# USB_IF_STM_Lpt_v3.net
KiCad netlist of a schematic drawn in EAGLE
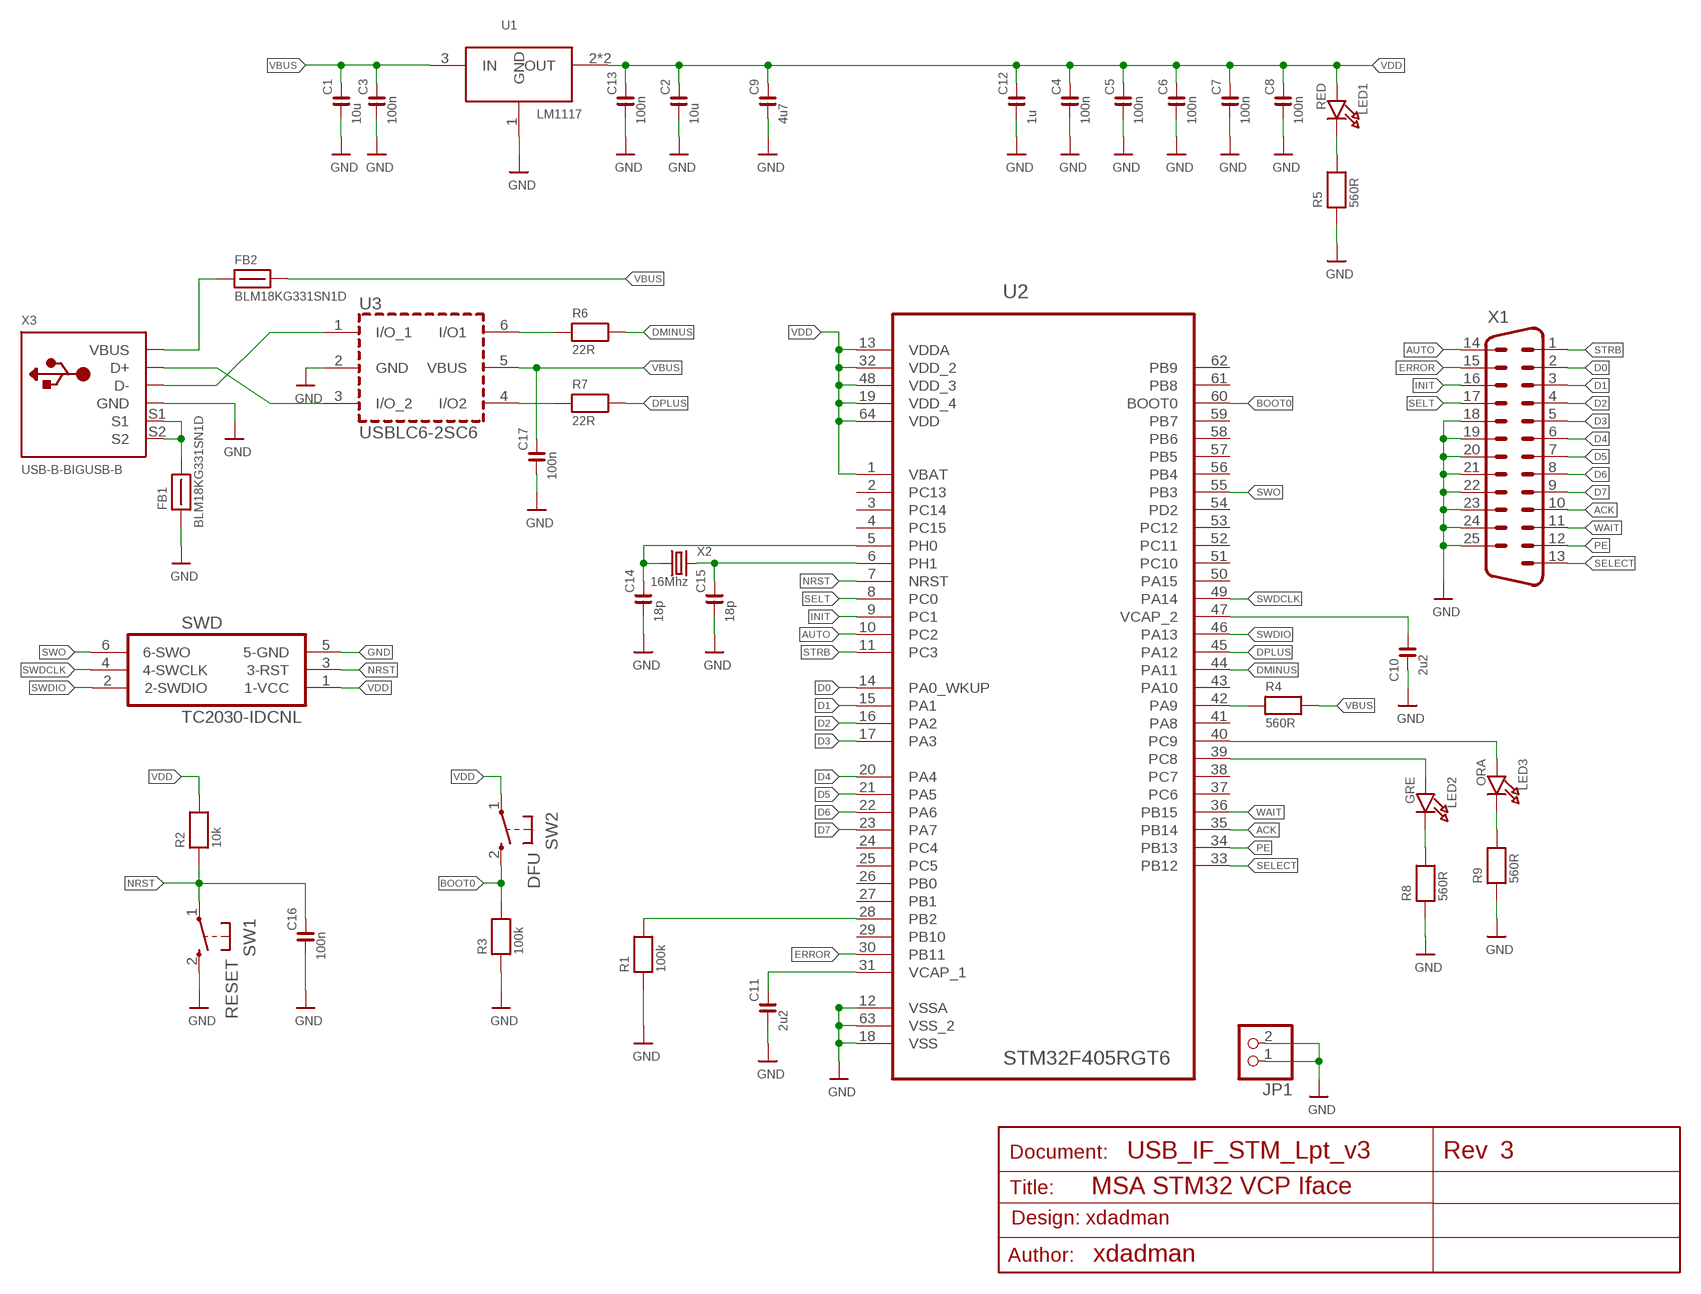
[diagram p0: schematic, sheet 1]

(export (version "E")
  (design (tool "Eeschema 10.0.6"))
  (components
    (comp (ref "C1")
      (value "10u")
      (footprint "eagle-import:C1206")
      (libsource (lib "eagle-import") (part "CC120610U"))
    )
    (comp (ref "C2")
      (value "10u")
      (footprint "eagle-import:C1206")
      (libsource (lib "eagle-import") (part "CC120610U"))
    )
    (comp (ref "C3")
      (value "100n")
      (footprint "eagle-import:C0603")
      (libsource (lib "eagle-import") (part "CC0603100NF"))
    )
    (comp (ref "C4")
      (value "100n")
      (footprint "eagle-import:C0603")
      (libsource (lib "eagle-import") (part "CC0603100NF"))
    )
    (comp (ref "C5")
      (value "100n")
      (footprint "eagle-import:C0603")
      (libsource (lib "eagle-import") (part "CC0603100NF"))
    )
    (comp (ref "C6")
      (value "100n")
      (footprint "eagle-import:C0603")
      (libsource (lib "eagle-import") (part "CC0603100NF"))
    )
    (comp (ref "C7")
      (value "100n")
      (footprint "eagle-import:C0603")
      (libsource (lib "eagle-import") (part "CC0603100NF"))
    )
    (comp (ref "C8")
      (value "100n")
      (footprint "eagle-import:C0603")
      (libsource (lib "eagle-import") (part "CC0603100NF"))
    )
    (comp (ref "C9")
      (value "4u7")
      (footprint "eagle-import:C0603")
      (libsource (lib "eagle-import") (part "CC06034U7"))
    )
    (comp (ref "C10")
      (value "2u2")
      (footprint "eagle-import:C0603")
      (libsource (lib "eagle-import") (part "CC06032U2"))
    )
    (comp (ref "C11")
      (value "2u2")
      (footprint "eagle-import:C0603")
      (libsource (lib "eagle-import") (part "CC06032U2"))
    )
    (comp (ref "C12")
      (value "1u")
      (footprint "eagle-import:C0603")
      (libsource (lib "eagle-import") (part "CC06031UF"))
    )
    (comp (ref "C13")
      (value "100n")
      (footprint "eagle-import:C0603")
      (libsource (lib "eagle-import") (part "CC0603100NF"))
    )
    (comp (ref "C14")
      (value "18p")
      (footprint "eagle-import:C0603")
      (libsource (lib "eagle-import") (part "CC060318PF"))
    )
    (comp (ref "C15")
      (value "18p")
      (footprint "eagle-import:C0603")
      (libsource (lib "eagle-import") (part "CC060318PF"))
    )
    (comp (ref "C16")
      (value "100n")
      (footprint "eagle-import:C0603")
      (libsource (lib "eagle-import") (part "CC0603100NF"))
    )
    (comp (ref "C17")
      (value "100n")
      (footprint "eagle-import:C0603")
      (libsource (lib "eagle-import") (part "CC0603100NF"))
    )
    (comp (ref "FB1")
      (value "BLM18KG331SN1D")
      (footprint "eagle-import:R0603")
      (libsource (lib "eagle-import") (part "FBEAD0603BLM18KG331SN1D"))
    )
    (comp (ref "FB2")
      (value "BLM18KG331SN1D")
      (footprint "eagle-import:R0603")
      (libsource (lib "eagle-import") (part "FBEAD0603BLM18KG331SN1D"))
    )
    (comp (ref "JP1")
      (value "PINHD-1X2")
      (footprint "eagle-import:1X02")
      (libsource (lib "eagle-import") (part "PINHD-1X2"))
    )
    (comp (ref "LED1")
      (value "RED")
      (footprint "eagle-import:CHIPLED_0603")
      (libsource (lib "eagle-import") (part "LED_0603_RED0603"))
    )
    (comp (ref "LED2")
      (value "GRE")
      (footprint "eagle-import:CHIPLED_0603")
      (libsource (lib "eagle-import") (part "LED_0603_GRE0603"))
    )
    (comp (ref "LED3")
      (value "ORA")
      (footprint "eagle-import:CHIPLED_0603")
      (libsource (lib "eagle-import") (part "LED_0603_YEL0603"))
    )
    (comp (ref "R1")
      (value "100k")
      (footprint "eagle-import:R0603")
      (libsource (lib "eagle-import") (part "R0603100K"))
    )
    (comp (ref "R2")
      (value "10k")
      (footprint "eagle-import:0603-MINI")
      (libsource (lib "eagle-import") (part "R060310K"))
    )
    (comp (ref "R3")
      (value "100k")
      (footprint "eagle-import:R0603")
      (libsource (lib "eagle-import") (part "R0603100K"))
    )
    (comp (ref "R4")
      (value "560R")
      (footprint "eagle-import:R0603")
      (libsource (lib "eagle-import") (part "R0603560R"))
    )
    (comp (ref "R5")
      (value "560R")
      (footprint "eagle-import:R0603")
      (libsource (lib "eagle-import") (part "R0603560R"))
    )
    (comp (ref "R6")
      (value "22R")
      (footprint "eagle-import:R0603")
      (libsource (lib "eagle-import") (part "R060322R"))
    )
    (comp (ref "R7")
      (value "22R")
      (footprint "eagle-import:R0603")
      (libsource (lib "eagle-import") (part "R060322R"))
    )
    (comp (ref "R8")
      (value "560R")
      (footprint "eagle-import:R0603")
      (libsource (lib "eagle-import") (part "R0603560R"))
    )
    (comp (ref "R9")
      (value "560R")
      (footprint "eagle-import:R0603")
      (libsource (lib "eagle-import") (part "R0603560R"))
    )
    (comp (ref "SW1")
      (value "RESET")
      (footprint "eagle-import:TACTILE_6X3")
      (libsource (lib "eagle-import") (part "TACTILE_SWITCH_R6X3"))
    )
    (comp (ref "SW2")
      (value "DFU")
      (footprint "eagle-import:TACTILE_6X3")
      (libsource (lib "eagle-import") (part "TACTILE_SWITCH_R6X3"))
    )
    (comp (ref "SWD")
      (value "TC2030-IDCNL")
      (footprint "eagle-import:TC2030-IDC-NL")
      (libsource (lib "eagle-import") (part "TC2030-IDCNL"))
    )
    (comp (ref "U1")
      (value "LM1117")
      (footprint "eagle-import:SOT223")
      (libsource (lib "eagle-import") (part "LM1117"))
    )
    (comp (ref "U2")
      (value "STM32F405RGT6")
      (footprint "eagle-import:QFP50P1200X1200X160-64N")
      (libsource (lib "eagle-import") (part "STM32F405RGT6"))
    )
    (comp (ref "U3")
      (value "USBLC6-2SC6")
      (footprint "eagle-import:SOT-23-6L")
      (libsource (lib "eagle-import") (part "USBLC6-2SC6"))
    )
    (comp (ref "X1")
      (value "M25D")
      (footprint "eagle-import:M25D")
      (libsource (lib "eagle-import") (part "M25D"))
    )
    (comp (ref "X2")
      (value "16Mhz")
      (footprint "eagle-import:ABRACON_ABM7")
      (libsource (lib "eagle-import") (part "ABM7-16MHZ"))
    )
    (comp (ref "X3")
      (value "USB-B-BIGUSB-B")
      (footprint "eagle-import:USB-B-PTH")
      (libsource (lib "eagle-import") (part "USB-B-BIGUSB-B"))
    )
  )
  (nets
    (net (code "1") (name "ACK") (class "Default")
      (node (ref "U2") (pin "35") (pinfunction "PB14_35") (pintype "bidirectional"))
      (node (ref "X1") (pin "10") (pinfunction "10_10") (pintype "passive"))
    )
    (net (code "2") (name "AUTO") (class "Default")
      (node (ref "U2") (pin "10") (pinfunction "PC2_10") (pintype "bidirectional"))
      (node (ref "X1") (pin "14") (pinfunction "14_14") (pintype "passive"))
    )
    (net (code "3") (name "BOOT0") (class "Default")
      (node (ref "R3") (pin "2") (pinfunction "2_2") (pintype "passive"))
      (node (ref "SW2") (pin "2") (pinfunction "2_2") (pintype "passive"))
      (node (ref "U2") (pin "60") (pinfunction "BOOT0_60") (pintype "passive"))
    )
    (net (code "4") (name "D0") (class "Default")
      (node (ref "U2") (pin "14") (pinfunction "PA0_WKUP_14") (pintype "passive"))
      (node (ref "X1") (pin "2") (pinfunction "2_2") (pintype "passive"))
    )
    (net (code "5") (name "D1") (class "Default")
      (node (ref "U2") (pin "15") (pinfunction "PA1_15") (pintype "bidirectional"))
      (node (ref "X1") (pin "3") (pinfunction "3_3") (pintype "passive"))
    )
    (net (code "6") (name "D2") (class "Default")
      (node (ref "U2") (pin "16") (pinfunction "PA2_16") (pintype "bidirectional"))
      (node (ref "X1") (pin "4") (pinfunction "4_4") (pintype "passive"))
    )
    (net (code "7") (name "D3") (class "Default")
      (node (ref "U2") (pin "17") (pinfunction "PA3_17") (pintype "bidirectional"))
      (node (ref "X1") (pin "5") (pinfunction "5_5") (pintype "passive"))
    )
    (net (code "8") (name "D4") (class "Default")
      (node (ref "U2") (pin "20") (pinfunction "PA4_20") (pintype "bidirectional"))
      (node (ref "X1") (pin "6") (pinfunction "6_6") (pintype "passive"))
    )
    (net (code "9") (name "D5") (class "Default")
      (node (ref "U2") (pin "21") (pinfunction "PA5_21") (pintype "bidirectional"))
      (node (ref "X1") (pin "7") (pinfunction "7_7") (pintype "passive"))
    )
    (net (code "10") (name "D6") (class "Default")
      (node (ref "U2") (pin "22") (pinfunction "PA6_22") (pintype "bidirectional"))
      (node (ref "X1") (pin "8") (pinfunction "8_8") (pintype "passive"))
    )
    (net (code "11") (name "D7") (class "Default")
      (node (ref "U2") (pin "23") (pinfunction "PA7_23") (pintype "bidirectional"))
      (node (ref "X1") (pin "9") (pinfunction "9_9") (pintype "passive"))
    )
    (net (code "12") (name "DMINUS") (class "Default")
      (node (ref "R6") (pin "2") (pinfunction "2_2") (pintype "passive"))
      (node (ref "U2") (pin "44") (pinfunction "PA11_44") (pintype "bidirectional"))
    )
    (net (code "13") (name "DPLUS") (class "Default")
      (node (ref "R7") (pin "2") (pinfunction "2_2") (pintype "passive"))
      (node (ref "U2") (pin "45") (pinfunction "PA12_45") (pintype "bidirectional"))
    )
    (net (code "14") (name "ERROR") (class "Default")
      (node (ref "U2") (pin "30") (pinfunction "PB11_30") (pintype "bidirectional"))
      (node (ref "X1") (pin "15") (pinfunction "15_15") (pintype "passive"))
    )
    (net (code "15") (name "GND") (class "Default")
      (node (ref "C1") (pin "1") (pinfunction "1_1") (pintype "passive"))
      (node (ref "C10") (pin "1") (pinfunction "1_1") (pintype "passive"))
      (node (ref "C11") (pin "1") (pinfunction "1_1") (pintype "passive"))
      (node (ref "C12") (pin "1") (pinfunction "1_1") (pintype "passive"))
      (node (ref "C13") (pin "1") (pinfunction "1_1") (pintype "passive"))
      (node (ref "C14") (pin "1") (pinfunction "1_1") (pintype "passive"))
      (node (ref "C15") (pin "1") (pinfunction "1_1") (pintype "passive"))
      (node (ref "C16") (pin "1") (pinfunction "1_1") (pintype "passive"))
      (node (ref "C17") (pin "1") (pinfunction "1_1") (pintype "passive"))
      (node (ref "C2") (pin "1") (pinfunction "1_1") (pintype "passive"))
      (node (ref "C3") (pin "1") (pinfunction "1_1") (pintype "passive"))
      (node (ref "C4") (pin "1") (pinfunction "1_1") (pintype "passive"))
      (node (ref "C5") (pin "1") (pinfunction "1_1") (pintype "passive"))
      (node (ref "C6") (pin "1") (pinfunction "1_1") (pintype "passive"))
      (node (ref "C7") (pin "1") (pinfunction "1_1") (pintype "passive"))
      (node (ref "C8") (pin "1") (pinfunction "1_1") (pintype "passive"))
      (node (ref "C9") (pin "1") (pinfunction "1_1") (pintype "passive"))
      (node (ref "FB1") (pin "1") (pinfunction "1_1") (pintype "passive"))
      (node (ref "JP1") (pin "1") (pinfunction "1_1") (pintype "passive"))
      (node (ref "JP1") (pin "2") (pinfunction "2_2") (pintype "passive"))
      (node (ref "R1") (pin "1") (pinfunction "1_1") (pintype "passive"))
      (node (ref "R3") (pin "1") (pinfunction "1_1") (pintype "passive"))
      (node (ref "R5") (pin "1") (pinfunction "1_1") (pintype "passive"))
      (node (ref "R8") (pin "1") (pinfunction "1_1") (pintype "passive"))
      (node (ref "R9") (pin "1") (pinfunction "1_1") (pintype "passive"))
      (node (ref "SW1") (pin "2") (pinfunction "2_2") (pintype "passive"))
      (node (ref "SWD") (pin "5") (pinfunction "5-GND_5") (pintype "passive"))
      (node (ref "U1") (pin "1") (pinfunction "GND_1") (pintype "bidirectional"))
      (node (ref "U2") (pin "12") (pinfunction "VSSA_12") (pintype "power_in"))
      (node (ref "U2") (pin "18") (pinfunction "VSS_18") (pintype "power_in"))
      (node (ref "U2") (pin "63") (pinfunction "VSS_2_63") (pintype "power_in"))
      (node (ref "U3") (pin "2") (pinfunction "GND_2") (pintype "bidirectional"))
      (node (ref "X1") (pin "18") (pinfunction "18_18") (pintype "passive"))
      (node (ref "X1") (pin "19") (pinfunction "19_19") (pintype "passive"))
      (node (ref "X1") (pin "20") (pinfunction "20_20") (pintype "passive"))
      (node (ref "X1") (pin "21") (pinfunction "21_21") (pintype "passive"))
      (node (ref "X1") (pin "22") (pinfunction "22_22") (pintype "passive"))
      (node (ref "X1") (pin "23") (pinfunction "23_23") (pintype "passive"))
      (node (ref "X1") (pin "24") (pinfunction "24_24") (pintype "passive"))
      (node (ref "X1") (pin "25") (pinfunction "25_25") (pintype "passive"))
      (node (ref "X3") (pin "GND") (pinfunction "GND_GND") (pintype "power_in"))
    )
    (net (code "16") (name "INIT") (class "Default")
      (node (ref "U2") (pin "9") (pinfunction "PC1_9") (pintype "bidirectional"))
      (node (ref "X1") (pin "16") (pinfunction "16_16") (pintype "passive"))
    )
    (net (code "17") (name "NRST") (class "Default")
      (node (ref "C16") (pin "2") (pinfunction "2_2") (pintype "passive"))
      (node (ref "R2") (pin "1") (pinfunction "1_1") (pintype "passive"))
      (node (ref "SW1") (pin "1") (pinfunction "1_1") (pintype "passive"))
      (node (ref "SWD") (pin "3") (pinfunction "3-RST_3") (pintype "passive"))
      (node (ref "U2") (pin "7") (pinfunction "NRST_7") (pintype "passive"))
    )
    (net (code "18") (name "Net-(FB1-Pad2)") (class "Default")
      (node (ref "FB1") (pin "2") (pinfunction "2_2") (pintype "passive"))
      (node (ref "X3") (pin "S1") (pinfunction "S1_S1") (pintype "bidirectional"))
      (node (ref "X3") (pin "S2") (pinfunction "S2_S2") (pintype "bidirectional"))
    )
    (net (code "19") (name "Net-(FB2-Pad1)") (class "Default")
      (node (ref "FB2") (pin "1") (pinfunction "1_1") (pintype "passive"))
      (node (ref "X3") (pin "VBUS") (pinfunction "VBUS_VBUS") (pintype "power_in"))
    )
    (net (code "20") (name "Net-(LED1-PadC)") (class "Default")
      (node (ref "LED1") (pin "C") (pinfunction "C_C") (pintype "passive"))
      (node (ref "R5") (pin "2") (pinfunction "2_2") (pintype "passive"))
    )
    (net (code "21") (name "Net-(LED2-PadC)") (class "Default")
      (node (ref "LED2") (pin "C") (pinfunction "C_C") (pintype "passive"))
      (node (ref "R8") (pin "2") (pinfunction "2_2") (pintype "passive"))
    )
    (net (code "22") (name "Net-(LED3-PadC)") (class "Default")
      (node (ref "LED3") (pin "C") (pinfunction "C_C") (pintype "passive"))
      (node (ref "R9") (pin "2") (pinfunction "2_2") (pintype "passive"))
    )
    (net (code "23") (name "Net-(U2-PA9)") (class "Default")
      (node (ref "R4") (pin "1") (pinfunction "1_1") (pintype "passive"))
      (node (ref "U2") (pin "42") (pinfunction "PA9_42") (pintype "bidirectional"))
    )
    (net (code "24") (name "Net-(U2-PB2)") (class "Default")
      (node (ref "R1") (pin "2") (pinfunction "2_2") (pintype "passive"))
      (node (ref "U2") (pin "28") (pinfunction "PB2_28") (pintype "bidirectional"))
    )
    (net (code "25") (name "Net-(U2-PC8)") (class "Default")
      (node (ref "LED2") (pin "A") (pinfunction "A_A") (pintype "passive"))
      (node (ref "U2") (pin "39") (pinfunction "PC8_39") (pintype "bidirectional"))
    )
    (net (code "26") (name "Net-(U2-PC9)") (class "Default")
      (node (ref "LED3") (pin "A") (pinfunction "A_A") (pintype "passive"))
      (node (ref "U2") (pin "40") (pinfunction "PC9_40") (pintype "bidirectional"))
    )
    (net (code "27") (name "Net-(U2-PH0)") (class "Default")
      (node (ref "C14") (pin "2") (pinfunction "2_2") (pintype "passive"))
      (node (ref "U2") (pin "5") (pinfunction "PH0_5") (pintype "bidirectional"))
      (node (ref "X2") (pin "P$1") (pinfunction "1_P$1") (pintype "passive"))
    )
    (net (code "28") (name "Net-(U2-PH1)") (class "Default")
      (node (ref "C15") (pin "2") (pinfunction "2_2") (pintype "passive"))
      (node (ref "U2") (pin "6") (pinfunction "PH1_6") (pintype "bidirectional"))
      (node (ref "X2") (pin "P$2") (pinfunction "2_P$2") (pintype "passive"))
    )
    (net (code "29") (name "Net-(U2-VCAP_1)") (class "Default")
      (node (ref "C11") (pin "2") (pinfunction "2_2") (pintype "passive"))
      (node (ref "U2") (pin "31") (pinfunction "VCAP_1_31") (pintype "passive"))
    )
    (net (code "30") (name "Net-(U2-VCAP_2)") (class "Default")
      (node (ref "C10") (pin "2") (pinfunction "2_2") (pintype "passive"))
      (node (ref "U2") (pin "47") (pinfunction "VCAP_2_47") (pintype "passive"))
    )
    (net (code "31") (name "Net-(U3-I{slash}O1)") (class "Default")
      (node (ref "R6") (pin "1") (pinfunction "1_1") (pintype "passive"))
      (node (ref "U3") (pin "6") (pinfunction "I/O1_6") (pintype "bidirectional"))
    )
    (net (code "32") (name "Net-(U3-I{slash}O2)") (class "Default")
      (node (ref "R7") (pin "1") (pinfunction "1_1") (pintype "passive"))
      (node (ref "U3") (pin "4") (pinfunction "I/O2_4") (pintype "bidirectional"))
    )
    (net (code "33") (name "Net-(U3-I{slash}O_1)") (class "Default")
      (node (ref "U3") (pin "1") (pinfunction "I/O_1_1") (pintype "bidirectional"))
      (node (ref "X3") (pin "D-") (pinfunction "D-_D-") (pintype "bidirectional"))
    )
    (net (code "34") (name "Net-(U3-I{slash}O_2)") (class "Default")
      (node (ref "U3") (pin "3") (pinfunction "I/O_2_3") (pintype "bidirectional"))
      (node (ref "X3") (pin "D+") (pinfunction "D+_D+") (pintype "bidirectional"))
    )
    (net (code "35") (name "PE") (class "Default")
      (node (ref "U2") (pin "34") (pinfunction "PB13_34") (pintype "bidirectional"))
      (node (ref "X1") (pin "12") (pinfunction "12_12") (pintype "passive"))
    )
    (net (code "36") (name "SELECT") (class "Default")
      (node (ref "U2") (pin "33") (pinfunction "PB12_33") (pintype "bidirectional"))
      (node (ref "X1") (pin "13") (pinfunction "13_13") (pintype "passive"))
    )
    (net (code "37") (name "SELT") (class "Default")
      (node (ref "U2") (pin "8") (pinfunction "PC0_8") (pintype "bidirectional"))
      (node (ref "X1") (pin "17") (pinfunction "17_17") (pintype "passive"))
    )
    (net (code "38") (name "STRB") (class "Default")
      (node (ref "U2") (pin "11") (pinfunction "PC3_11") (pintype "bidirectional"))
      (node (ref "X1") (pin "1") (pinfunction "1_1") (pintype "passive"))
    )
    (net (code "39") (name "SWDCLK") (class "Default")
      (node (ref "SWD") (pin "4") (pinfunction "4-SWCLK_4") (pintype "passive"))
      (node (ref "U2") (pin "49") (pinfunction "PA14_49") (pintype "bidirectional"))
    )
    (net (code "40") (name "SWDIO") (class "Default")
      (node (ref "SWD") (pin "2") (pinfunction "2-SWDIO_2") (pintype "passive"))
      (node (ref "U2") (pin "46") (pinfunction "PA13_46") (pintype "bidirectional"))
    )
    (net (code "41") (name "SWO") (class "Default")
      (node (ref "SWD") (pin "6") (pinfunction "6-SWO_6") (pintype "passive"))
      (node (ref "U2") (pin "55") (pinfunction "PB3_55") (pintype "bidirectional"))
    )
    (net (code "42") (name "VBUS") (class "Default")
      (node (ref "C1") (pin "2") (pinfunction "2_2") (pintype "passive"))
      (node (ref "C17") (pin "2") (pinfunction "2_2") (pintype "passive"))
      (node (ref "C3") (pin "2") (pinfunction "2_2") (pintype "passive"))
      (node (ref "FB2") (pin "2") (pinfunction "2_2") (pintype "passive"))
      (node (ref "R4") (pin "2") (pinfunction "2_2") (pintype "passive"))
      (node (ref "U1") (pin "3") (pinfunction "IN_3") (pintype "bidirectional"))
      (node (ref "U3") (pin "5") (pinfunction "VBUS_5") (pintype "bidirectional"))
    )
    (net (code "43") (name "VDD") (class "Default")
      (node (ref "C12") (pin "2") (pinfunction "2_2") (pintype "passive"))
      (node (ref "C13") (pin "2") (pinfunction "2_2") (pintype "passive"))
      (node (ref "C2") (pin "2") (pinfunction "2_2") (pintype "passive"))
      (node (ref "C4") (pin "2") (pinfunction "2_2") (pintype "passive"))
      (node (ref "C5") (pin "2") (pinfunction "2_2") (pintype "passive"))
      (node (ref "C6") (pin "2") (pinfunction "2_2") (pintype "passive"))
      (node (ref "C7") (pin "2") (pinfunction "2_2") (pintype "passive"))
      (node (ref "C8") (pin "2") (pinfunction "2_2") (pintype "passive"))
      (node (ref "C9") (pin "2") (pinfunction "2_2") (pintype "passive"))
      (node (ref "LED1") (pin "A") (pinfunction "A_A") (pintype "passive"))
      (node (ref "R2") (pin "2") (pinfunction "2_2") (pintype "passive"))
      (node (ref "SW2") (pin "1") (pinfunction "1_1") (pintype "passive"))
      (node (ref "SWD") (pin "1") (pinfunction "1-VCC_1") (pintype "passive"))
      (node (ref "U1") (pin "2") (pinfunction "OUT_2") (pintype "bidirectional"))
      (node (ref "U1") (pin "4") (pinfunction "OUT_4") (pintype "bidirectional"))
      (node (ref "U2") (pin "1") (pinfunction "VBAT_1") (pintype "passive"))
      (node (ref "U2") (pin "13") (pinfunction "VDDA_13") (pintype "power_in"))
      (node (ref "U2") (pin "19") (pinfunction "VDD_4_19") (pintype "power_in"))
      (node (ref "U2") (pin "32") (pinfunction "VDD_2_32") (pintype "power_in"))
      (node (ref "U2") (pin "48") (pinfunction "VDD_3_48") (pintype "power_in"))
      (node (ref "U2") (pin "64") (pinfunction "VDD_64") (pintype "power_in"))
    )
    (net (code "44") (name "WAIT") (class "Default")
      (node (ref "U2") (pin "36") (pinfunction "PB15_36") (pintype "bidirectional"))
      (node (ref "X1") (pin "11") (pinfunction "11_11") (pintype "passive"))
    )
    (net (code "45") (name "unconnected-(U2-PA8-Pad41)") (class "Default")
      (node (ref "U2") (pin "41") (pinfunction "PA8_41") (pintype "bidirectional"))
    )
    (net (code "46") (name "unconnected-(U2-PA10-Pad43)") (class "Default")
      (node (ref "U2") (pin "43") (pinfunction "PA10_43") (pintype "bidirectional"))
    )
    (net (code "47") (name "unconnected-(U2-PA15-Pad50)") (class "Default")
      (node (ref "U2") (pin "50") (pinfunction "PA15_50") (pintype "bidirectional"))
    )
    (net (code "48") (name "unconnected-(U2-PB0-Pad26)") (class "Default")
      (node (ref "U2") (pin "26") (pinfunction "PB0_26") (pintype "bidirectional"))
    )
    (net (code "49") (name "unconnected-(U2-PB1-Pad27)") (class "Default")
      (node (ref "U2") (pin "27") (pinfunction "PB1_27") (pintype "bidirectional"))
    )
    (net (code "50") (name "unconnected-(U2-PB4-Pad56)") (class "Default")
      (node (ref "U2") (pin "56") (pinfunction "PB4_56") (pintype "bidirectional"))
    )
    (net (code "51") (name "unconnected-(U2-PB5-Pad57)") (class "Default")
      (node (ref "U2") (pin "57") (pinfunction "PB5_57") (pintype "bidirectional"))
    )
    (net (code "52") (name "unconnected-(U2-PB6-Pad58)") (class "Default")
      (node (ref "U2") (pin "58") (pinfunction "PB6_58") (pintype "bidirectional"))
    )
    (net (code "53") (name "unconnected-(U2-PB7-Pad59)") (class "Default")
      (node (ref "U2") (pin "59") (pinfunction "PB7_59") (pintype "bidirectional"))
    )
    (net (code "54") (name "unconnected-(U2-PB8-Pad61)") (class "Default")
      (node (ref "U2") (pin "61") (pinfunction "PB8_61") (pintype "bidirectional"))
    )
    (net (code "55") (name "unconnected-(U2-PB9-Pad62)") (class "Default")
      (node (ref "U2") (pin "62") (pinfunction "PB9_62") (pintype "bidirectional"))
    )
    (net (code "56") (name "unconnected-(U2-PB10-Pad29)") (class "Default")
      (node (ref "U2") (pin "29") (pinfunction "PB10_29") (pintype "bidirectional"))
    )
    (net (code "57") (name "unconnected-(U2-PC4-Pad24)") (class "Default")
      (node (ref "U2") (pin "24") (pinfunction "PC4_24") (pintype "bidirectional"))
    )
    (net (code "58") (name "unconnected-(U2-PC5-Pad25)") (class "Default")
      (node (ref "U2") (pin "25") (pinfunction "PC5_25") (pintype "bidirectional"))
    )
    (net (code "59") (name "unconnected-(U2-PC6-Pad37)") (class "Default")
      (node (ref "U2") (pin "37") (pinfunction "PC6_37") (pintype "bidirectional"))
    )
    (net (code "60") (name "unconnected-(U2-PC7-Pad38)") (class "Default")
      (node (ref "U2") (pin "38") (pinfunction "PC7_38") (pintype "bidirectional"))
    )
    (net (code "61") (name "unconnected-(U2-PC10-Pad51)") (class "Default")
      (node (ref "U2") (pin "51") (pinfunction "PC10_51") (pintype "bidirectional"))
    )
    (net (code "62") (name "unconnected-(U2-PC11-Pad52)") (class "Default")
      (node (ref "U2") (pin "52") (pinfunction "PC11_52") (pintype "bidirectional"))
    )
    (net (code "63") (name "unconnected-(U2-PC12-Pad53)") (class "Default")
      (node (ref "U2") (pin "53") (pinfunction "PC12_53") (pintype "bidirectional"))
    )
    (net (code "64") (name "unconnected-(U2-PC13-Pad2)") (class "Default")
      (node (ref "U2") (pin "2") (pinfunction "PC13_2") (pintype "bidirectional"))
    )
    (net (code "65") (name "unconnected-(U2-PC14-Pad3)") (class "Default")
      (node (ref "U2") (pin "3") (pinfunction "PC14_3") (pintype "bidirectional"))
    )
    (net (code "66") (name "unconnected-(U2-PC15-Pad4)") (class "Default")
      (node (ref "U2") (pin "4") (pinfunction "PC15_4") (pintype "bidirectional"))
    )
    (net (code "67") (name "unconnected-(U2-PD2-Pad54)") (class "Default")
      (node (ref "U2") (pin "54") (pinfunction "PD2_54") (pintype "bidirectional"))
    )
  )
)
